# Current_Measurement_CAS5000.net
KiCad netlist of a schematic drawn in Altium Designer
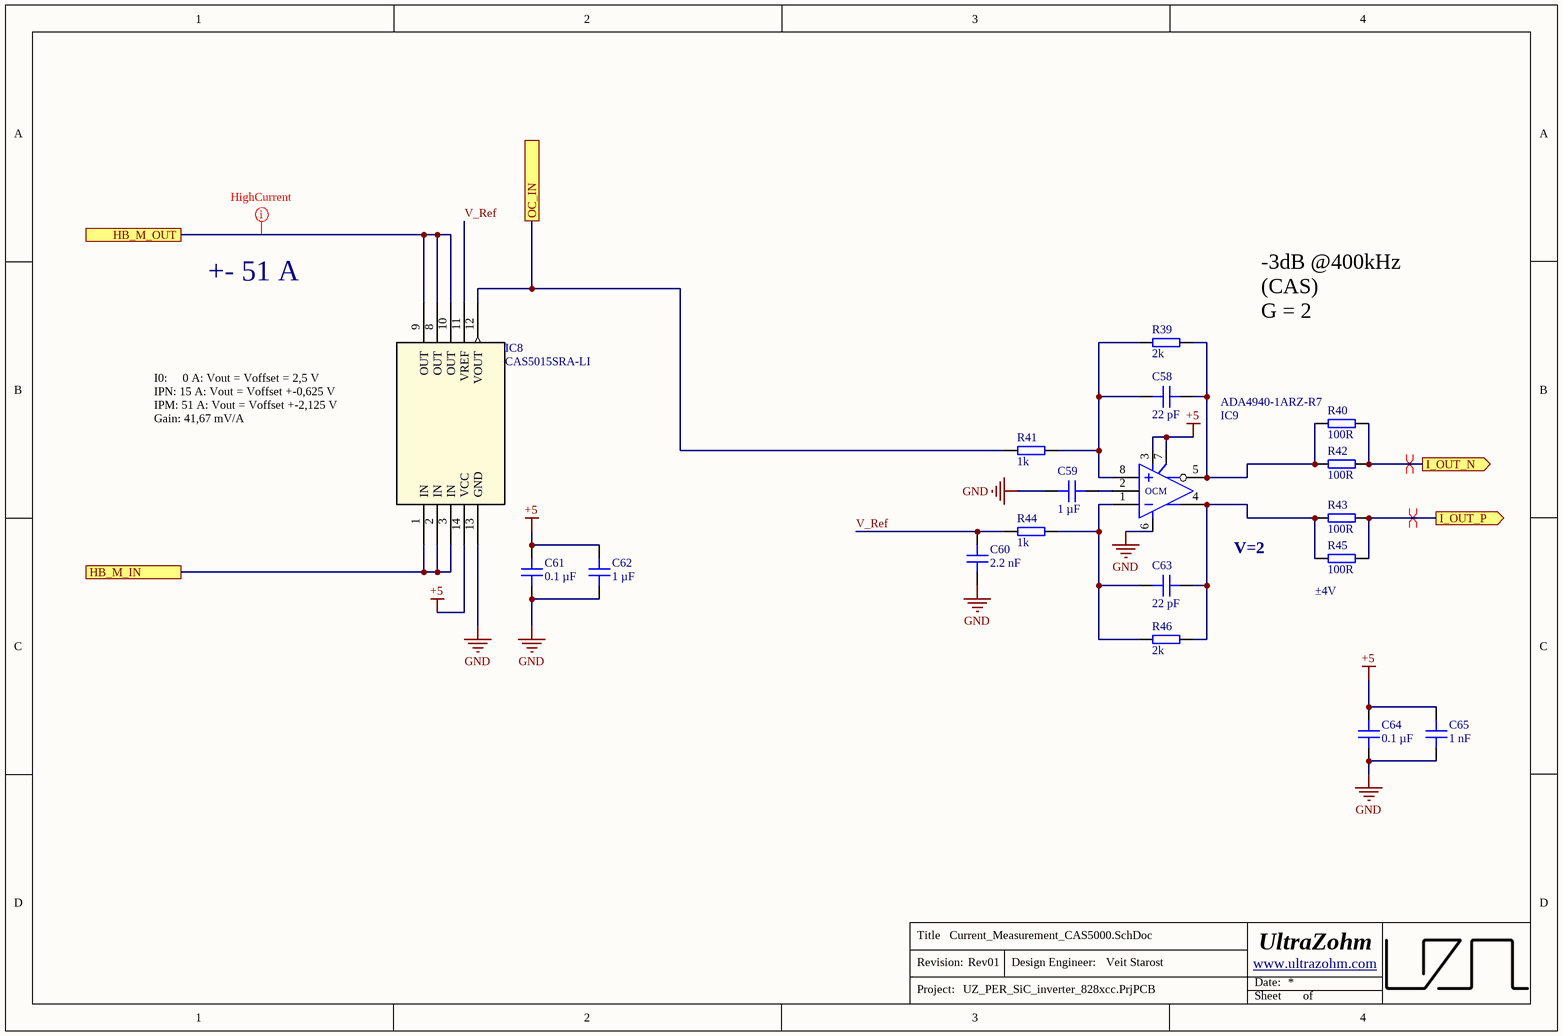
[diagram p0: Current_Measurement_CAS5000.SchDoc]

(export (version "E")
  (design (tool "Eeschema 10.0.6"))
  (components
    (comp (ref "C58")
      (value "22 pF")
      (footprint "C_0603")
      (description "Capacitor 0603, 50 VDC, 22 pF, X7R")
      (fields
        (field (name "MANUFACTURER PART NUMBER") "C0603C220J5RACTU")
        (field (name "MANUFACTURER") "KEMET")
        (field (name "CREATED FROM") "MGremer")
      )
      (libsource (lib "user") (part "Capacitor"))
    )
    (comp (ref "C59")
      (value "1 µF")
      (footprint "C_0603")
      (description "50V 1uF X7R ±10% 0603 Multilayer Ceramic Capacitors MLCC - SMD/SMT ROHS")
      (fields
        (field (name "MANUFACTURER PART NUMBER") "UMK107AB7105KA-T")
        (field (name "MANUFACTURER") "Taiyo Yuden")
        (field (name "CREATED FROM") "NDiringer")
      )
      (libsource (lib "user") (part "Capacitor"))
    )
    (comp (ref "C60")
      (value "2.2 nF")
      (footprint "C_0603")
      (description "Capacitor 0603, 50 VDC, 2.2 nF, X7R")
      (fields
        (field (name "MANUFACTURER PART NUMBER") "06035C222JAT2A")
        (field (name "MANUFACTURER") "AVX")
        (field (name "CREATED FROM") "MGremer")
      )
      (libsource (lib "user") (part "Capacitor"))
    )
    (comp (ref "C61")
      (value "0.1 µF")
      (footprint "C_0603")
      (description "Capacitor 0603, 50 VDC, 0.1 µF, X7R")
      (fields
        (field (name "MANUFACTURER PART NUMBER") "C0603X104K5RAC7411")
        (field (name "MANUFACTURER") "KEMET")
        (field (name "CREATED FROM") "MGremer")
      )
      (libsource (lib "user") (part "Capacitor"))
    )
    (comp (ref "C62")
      (value "1 µF")
      (footprint "C_0603")
      (description "50V 1uF X7R ±10% 0603 Multilayer Ceramic Capacitors MLCC - SMD/SMT ROHS")
      (fields
        (field (name "MANUFACTURER PART NUMBER") "UMK107AB7105KA-T")
        (field (name "MANUFACTURER") "Taiyo Yuden")
        (field (name "CREATED FROM") "NDiringer")
      )
      (libsource (lib "user") (part "Capacitor"))
    )
    (comp (ref "C63")
      (value "22 pF")
      (footprint "C_0603")
      (description "Capacitor 0603, 50 VDC, 22 pF, X7R")
      (fields
        (field (name "MANUFACTURER PART NUMBER") "C0603C220J5RACTU")
        (field (name "MANUFACTURER") "KEMET")
        (field (name "CREATED FROM") "MGremer")
      )
      (libsource (lib "user") (part "Capacitor"))
    )
    (comp (ref "C64")
      (value "0.1 µF")
      (footprint "C_0603")
      (description "Capacitor 0603, 50 VDC, 0.1 µF, X7R")
      (fields
        (field (name "MANUFACTURER PART NUMBER") "C0603X104K5RAC7411")
        (field (name "MANUFACTURER") "KEMET")
        (field (name "CREATED FROM") "MGremer")
      )
      (libsource (lib "user") (part "Capacitor"))
    )
    (comp (ref "C65")
      (value "1 nF")
      (footprint "C_0603")
      (description "Capacitor 0603, 50 VDC, 1 nF, NP0")
      (fields
        (field (name "MANUFACTURER PART NUMBER") "CC0603JRNPO9BN102")
        (field (name "MANUFACTURER") "YAGEO")
        (field (name "CREATED FROM") "AGeiger")
      )
      (libsource (lib "user") (part "Capacitor"))
    )
    (comp (ref "IC8")
      (value "CAS5015SRA-LI")
      (footprint "CAS50xxSRA")
      (description "15A, 1.1%, 400kHz")
      (fields
        (field (name "MANUFACTURER_PART_NUMBER") "CASR 15-NP")
        (field (name "MANUFACTURER") "Sensitec")
        (field (name "COPYRIGHT") "Copyright (C) 2022 Ultra Librarian. All rights reserved.")
        (field (name "CREATED FROM") "VStarost")
      )
      (libsource (lib "user") (part "CAS5050SRA"))
    )
    (comp (ref "IC9")
      (value "ADA4940-1ARZ-R7")
      (footprint "SOIC-8-N")
      (description "Differential ADC Driver")
      (fields (field (name "MANUFACTURER") "Analog Devices") (field (name "CREATED FROM") "MGremer"))
      (libsource (lib "user") (part "ADA4940-1ARZ"))
    )
    (comp (ref "R39")
      (value "2k")
      (footprint "RES 0603_1608")
      (description "SMD resistor 0.1%")
      (fields
        (field (name "MANUFACTURER PART NUMBER") "ERA-3VEB2001V")
        (field (name "MANUFACTURER") "Panasonic")
        (field (name "CREATED FROM") "MGremer")
      )
      (libsource (lib "user") (part "Resistor"))
    )
    (comp (ref "R40")
      (value "100R")
      (footprint "RES 0603_1608")
      (description "SMD resistor E24 series")
      (fields
        (field (name "MANUFACTURER PART NUMBER") "RK73B1JTTD101J")
        (field (name "MANUFACTURER") "KOA Speer")
        (field (name "CREATED FROM") "MGremer")
      )
      (libsource (lib "user") (part "Resistor"))
    )
    (comp (ref "R41")
      (value "1k")
      (footprint "RES 0603_1608")
      (description "SMD resistor 1%")
      (fields
        (field (name "MANUFACTURER PART NUMBER") "RC0603FR-071KL")
        (field (name "MANUFACTURER") "YAGEO")
        (field (name "CREATED FROM") "MGremer")
      )
      (libsource (lib "user") (part "Resistor"))
    )
    (comp (ref "R42")
      (value "100R")
      (footprint "RES 0603_1608")
      (description "SMD resistor E24 series")
      (fields
        (field (name "MANUFACTURER PART NUMBER") "RK73B1JTTD101J")
        (field (name "MANUFACTURER") "KOA Speer")
        (field (name "CREATED FROM") "MGremer")
      )
      (libsource (lib "user") (part "Resistor"))
    )
    (comp (ref "R43")
      (value "100R")
      (footprint "RES 0603_1608")
      (description "SMD resistor E24 series")
      (fields
        (field (name "MANUFACTURER PART NUMBER") "RK73B1JTTD101J")
        (field (name "MANUFACTURER") "KOA Speer")
        (field (name "CREATED FROM") "MGremer")
      )
      (libsource (lib "user") (part "Resistor"))
    )
    (comp (ref "R44")
      (value "1k")
      (footprint "RES 0603_1608")
      (description "SMD resistor 1%")
      (fields
        (field (name "MANUFACTURER PART NUMBER") "RC0603FR-071KL")
        (field (name "MANUFACTURER") "YAGEO")
        (field (name "CREATED FROM") "MGremer")
      )
      (libsource (lib "user") (part "Resistor"))
    )
    (comp (ref "R45")
      (value "100R")
      (footprint "RES 0603_1608")
      (description "SMD resistor E24 series")
      (fields
        (field (name "MANUFACTURER PART NUMBER") "RK73B1JTTD101J")
        (field (name "MANUFACTURER") "KOA Speer")
        (field (name "CREATED FROM") "MGremer")
      )
      (libsource (lib "user") (part "Resistor"))
    )
    (comp (ref "R46")
      (value "2k")
      (footprint "RES 0603_1608")
      (description "SMD resistor 0.1%")
      (fields
        (field (name "MANUFACTURER PART NUMBER") "ERA-3VEB2001V")
        (field (name "MANUFACTURER") "Panasonic")
        (field (name "CREATED FROM") "MGremer")
      )
      (libsource (lib "user") (part "Resistor"))
    )
  )
  (nets
    (net (code "1") (name "+5") (class "Default")
      (node (ref "C61") (pin "2") (pinfunction "2_2") (pintype "passive"))
      (node (ref "C62") (pin "1") (pinfunction "1_1") (pintype "passive"))
      (node (ref "C64") (pin "2") (pinfunction "2_2") (pintype "passive"))
      (node (ref "C65") (pin "2") (pinfunction "2_2") (pintype "passive"))
      (node (ref "IC8") (pin "14") (pinfunction "VCC_14") (pintype "power_in"))
      (node (ref "IC9") (pin "3") (pinfunction "V+_3") (pintype "passive"))
      (node (ref "IC9") (pin "7") (pinfunction "EN_7") (pintype "passive"))
    )
    (net (code "2") (name "/HB_M_IN") (class "Default")
      (node (ref "IC8") (pin "1") (pinfunction "IN_1") (pintype "passive"))
      (node (ref "IC8") (pin "2") (pinfunction "IN_2") (pintype "passive"))
      (node (ref "IC8") (pin "3") (pinfunction "IN_3") (pintype "passive"))
    )
    (net (code "3") (name "/HB_M_OUT") (class "Default")
      (node (ref "IC8") (pin "10") (pinfunction "OUT_10") (pintype "passive"))
      (node (ref "IC8") (pin "8") (pinfunction "OUT_8") (pintype "passive"))
      (node (ref "IC8") (pin "9") (pinfunction "OUT_9") (pintype "passive"))
    )
    (net (code "4") (name "/I_OUT_N") (class "Default")
      (node (ref "R40") (pin "2") (pinfunction "2_2") (pintype "passive"))
      (node (ref "R42") (pin "2") (pinfunction "2_2") (pintype "passive"))
    )
    (net (code "5") (name "/I_OUT_P") (class "Default")
      (node (ref "R43") (pin "2") (pinfunction "2_2") (pintype "passive"))
      (node (ref "R45") (pin "2") (pinfunction "2_2") (pintype "passive"))
    )
    (net (code "6") (name "/OC_IN") (class "Default")
      (node (ref "IC8") (pin "12") (pinfunction "VOUT_12") (pintype "output"))
      (node (ref "R41") (pin "1") (pinfunction "1_1") (pintype "passive"))
    )
    (net (code "7") (name "/V_Ref") (class "Default")
      (node (ref "C60") (pin "2") (pinfunction "2_2") (pintype "passive"))
      (node (ref "IC8") (pin "11") (pinfunction "VREF_11") (pintype "power_in"))
      (node (ref "R44") (pin "1") (pinfunction "1_1") (pintype "passive"))
    )
    (net (code "8") (name "GND") (class "Default")
      (node (ref "C59") (pin "1") (pinfunction "1_1") (pintype "passive"))
      (node (ref "C60") (pin "1") (pinfunction "1_1") (pintype "passive"))
      (node (ref "C61") (pin "1") (pinfunction "1_1") (pintype "passive"))
      (node (ref "C62") (pin "2") (pinfunction "2_2") (pintype "passive"))
      (node (ref "C64") (pin "1") (pinfunction "1_1") (pintype "passive"))
      (node (ref "C65") (pin "1") (pinfunction "1_1") (pintype "passive"))
      (node (ref "IC8") (pin "13") (pinfunction "GND_13") (pintype "passive"))
      (node (ref "IC9") (pin "6") (pinfunction "V-_6") (pintype "passive"))
    )
    (net (code "9") (name "Net-(C58-Pad2)") (class "Default")
      (node (ref "C58") (pin "2") (pinfunction "2_2") (pintype "passive"))
      (node (ref "IC9") (pin "5") (pinfunction "Out_5") (pintype "passive"))
      (node (ref "R39") (pin "2") (pinfunction "2_2") (pintype "passive"))
      (node (ref "R40") (pin "1") (pinfunction "1_1") (pintype "passive"))
      (node (ref "R42") (pin "1") (pinfunction "1_1") (pintype "passive"))
    )
    (net (code "10") (name "Net-(C63-Pad2)") (class "Default")
      (node (ref "C63") (pin "2") (pinfunction "2_2") (pintype "passive"))
      (node (ref "IC9") (pin "4") (pinfunction "Out_4") (pintype "passive"))
      (node (ref "R43") (pin "1") (pinfunction "1_1") (pintype "passive"))
      (node (ref "R45") (pin "1") (pinfunction "1_1") (pintype "passive"))
      (node (ref "R46") (pin "2") (pinfunction "2_2") (pintype "passive"))
    )
    (net (code "11") (name "Net-(IC9-+)") (class "Default")
      (node (ref "C58") (pin "1") (pinfunction "1_1") (pintype "passive"))
      (node (ref "IC9") (pin "8") (pinfunction "+_8") (pintype "passive"))
      (node (ref "R39") (pin "1") (pinfunction "1_1") (pintype "passive"))
      (node (ref "R41") (pin "2") (pinfunction "2_2") (pintype "passive"))
    )
    (net (code "12") (name "Net-(IC9--)") (class "Default")
      (node (ref "C63") (pin "1") (pinfunction "1_1") (pintype "passive"))
      (node (ref "IC9") (pin "1") (pinfunction "-_1") (pintype "passive"))
      (node (ref "R44") (pin "2") (pinfunction "2_2") (pintype "passive"))
      (node (ref "R46") (pin "1") (pinfunction "1_1") (pintype "passive"))
    )
    (net (code "13") (name "Net-(IC9-OCM)") (class "Default")
      (node (ref "C59") (pin "2") (pinfunction "2_2") (pintype "passive"))
      (node (ref "IC9") (pin "2") (pinfunction "OCM_2") (pintype "passive"))
    )
  )
)
